# Li-Fi_Receiver_Schematic.net
KiCad netlist of a schematic drawn in EAGLE
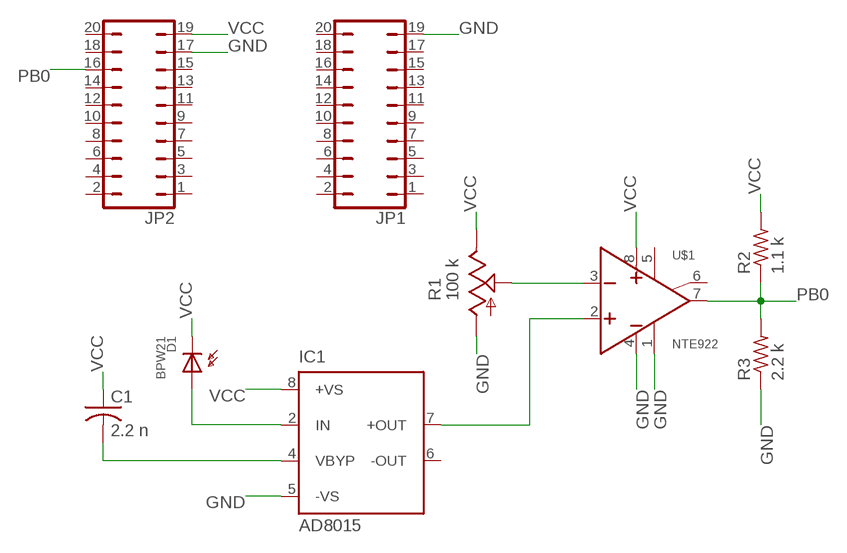
[diagram p0: schematic, sheet 1]

(export (version "E")
  (design (tool "Eeschema 10.0.6"))
  (components
    (comp (ref "C1")
      (value "2.2 n")
      (footprint "eagle-import:C0805")
      (libsource (lib "eagle-import") (part "C-USC0805"))
    )
    (comp (ref "D1")
      (value "BPW21")
      (footprint "eagle-import:TO-5")
      (libsource (lib "eagle-import") (part "BPW21"))
    )
    (comp (ref "IC1")
      (value "AD8015")
      (footprint "eagle-import:SO8")
      (fields (field (name "MPN") "AD8015ARZ"))
      (libsource (lib "eagle-import") (part "AD8015"))
    )
    (comp (ref "JP1")
      (value "JP10Q")
      (footprint "eagle-import:JP10Q")
      (libsource (lib "eagle-import") (part "JP10Q"))
    )
    (comp (ref "JP2")
      (value "JP10Q")
      (footprint "eagle-import:JP10Q")
      (libsource (lib "eagle-import") (part "JP10Q"))
    )
    (comp (ref "R1")
      (value "100 k")
      (footprint "eagle-import:B64Y")
      (libsource (lib "eagle-import") (part "TRIM_US-B64Y"))
    )
    (comp (ref "R2")
      (value "1.1 k")
      (footprint "eagle-import:M0805")
      (libsource (lib "eagle-import") (part "R-US_M0805"))
    )
    (comp (ref "R3")
      (value "2.2 k")
      (footprint "eagle-import:M0805")
      (libsource (lib "eagle-import") (part "R-US_M0805"))
    )
    (comp (ref "U$1")
      (value "NTE922")
      (footprint "eagle-import:DIP8")
      (libsource (lib "eagle-import") (part "NTE922"))
    )
  )
  (nets
    (net (code "1") (name "/GND") (class "Default")
      (node (ref "IC1") (pin "5") (pinfunction "-VS_5") (pintype "input"))
      (node (ref "JP1") (pin "19") (pinfunction "19_19") (pintype "passive"))
      (node (ref "JP2") (pin "17") (pinfunction "17_17") (pintype "passive"))
      (node (ref "R1") (pin "A") (pinfunction "A_A") (pintype "passive"))
      (node (ref "R3") (pin "1") (pinfunction "1_1") (pintype "passive"))
      (node (ref "U$1") (pin "1") (pinfunction "1_1") (pintype "bidirectional"))
      (node (ref "U$1") (pin "4") (pinfunction "4_4") (pintype "bidirectional"))
    )
    (net (code "2") (name "/PB0") (class "Default")
      (node (ref "JP2") (pin "16") (pinfunction "16_16") (pintype "passive"))
      (node (ref "R2") (pin "1") (pinfunction "1_1") (pintype "passive"))
      (node (ref "R3") (pin "2") (pinfunction "2_2") (pintype "passive"))
      (node (ref "U$1") (pin "7") (pinfunction "7_7") (pintype "bidirectional"))
    )
    (net (code "3") (name "/VCC") (class "Default")
      (node (ref "C1") (pin "1") (pinfunction "1_1") (pintype "passive"))
      (node (ref "D1") (pin "CATH") (pinfunction "CATH_CATH") (pintype "bidirectional"))
      (node (ref "IC1") (pin "8") (pinfunction "+VS_8") (pintype "input"))
      (node (ref "JP2") (pin "19") (pinfunction "19_19") (pintype "passive"))
      (node (ref "R1") (pin "E") (pinfunction "E_E") (pintype "passive"))
      (node (ref "R2") (pin "2") (pinfunction "2_2") (pintype "passive"))
      (node (ref "U$1") (pin "8") (pinfunction "8_8") (pintype "bidirectional"))
    )
    (net (code "4") (name "Net-(IC1-+OUT)") (class "Default")
      (node (ref "IC1") (pin "7") (pinfunction "+OUT_7") (pintype "output"))
      (node (ref "U$1") (pin "2") (pinfunction "2_2") (pintype "bidirectional"))
    )
    (net (code "5") (name "Net-(IC1-IN)") (class "Default")
      (node (ref "D1") (pin "AN") (pinfunction "AN_AN") (pintype "bidirectional"))
      (node (ref "IC1") (pin "2") (pinfunction "IN_2") (pintype "input"))
    )
    (net (code "6") (name "Net-(IC1-VBYP)") (class "Default")
      (node (ref "C1") (pin "2") (pinfunction "2_2") (pintype "passive"))
      (node (ref "IC1") (pin "4") (pinfunction "VBYP_4") (pintype "input"))
    )
    (net (code "7") (name "Net-(R1-PadS)") (class "Default")
      (node (ref "R1") (pin "S") (pinfunction "S_S") (pintype "passive"))
      (node (ref "U$1") (pin "3") (pinfunction "3_3") (pintype "bidirectional"))
    )
    (net (code "8") (name "unconnected-(IC1--OUT-Pad6)") (class "Default")
      (node (ref "IC1") (pin "6") (pinfunction "-OUT_6") (pintype "output"))
    )
    (net (code "9") (name "unconnected-(JP1-Pad1)") (class "Default")
      (node (ref "JP1") (pin "1") (pinfunction "1_1") (pintype "passive"))
    )
    (net (code "10") (name "unconnected-(JP1-Pad2)") (class "Default")
      (node (ref "JP1") (pin "2") (pinfunction "2_2") (pintype "passive"))
    )
    (net (code "11") (name "unconnected-(JP1-Pad3)") (class "Default")
      (node (ref "JP1") (pin "3") (pinfunction "3_3") (pintype "passive"))
    )
    (net (code "12") (name "unconnected-(JP1-Pad4)") (class "Default")
      (node (ref "JP1") (pin "4") (pinfunction "4_4") (pintype "passive"))
    )
    (net (code "13") (name "unconnected-(JP1-Pad5)") (class "Default")
      (node (ref "JP1") (pin "5") (pinfunction "5_5") (pintype "passive"))
    )
    (net (code "14") (name "unconnected-(JP1-Pad6)") (class "Default")
      (node (ref "JP1") (pin "6") (pinfunction "6_6") (pintype "passive"))
    )
    (net (code "15") (name "unconnected-(JP1-Pad7)") (class "Default")
      (node (ref "JP1") (pin "7") (pinfunction "7_7") (pintype "passive"))
    )
    (net (code "16") (name "unconnected-(JP1-Pad8)") (class "Default")
      (node (ref "JP1") (pin "8") (pinfunction "8_8") (pintype "passive"))
    )
    (net (code "17") (name "unconnected-(JP1-Pad9)") (class "Default")
      (node (ref "JP1") (pin "9") (pinfunction "9_9") (pintype "passive"))
    )
    (net (code "18") (name "unconnected-(JP1-Pad10)") (class "Default")
      (node (ref "JP1") (pin "10") (pinfunction "10_10") (pintype "passive"))
    )
    (net (code "19") (name "unconnected-(JP1-Pad11)") (class "Default")
      (node (ref "JP1") (pin "11") (pinfunction "11_11") (pintype "passive"))
    )
    (net (code "20") (name "unconnected-(JP1-Pad12)") (class "Default")
      (node (ref "JP1") (pin "12") (pinfunction "12_12") (pintype "passive"))
    )
    (net (code "21") (name "unconnected-(JP1-Pad13)") (class "Default")
      (node (ref "JP1") (pin "13") (pinfunction "13_13") (pintype "passive"))
    )
    (net (code "22") (name "unconnected-(JP1-Pad14)") (class "Default")
      (node (ref "JP1") (pin "14") (pinfunction "14_14") (pintype "passive"))
    )
    (net (code "23") (name "unconnected-(JP1-Pad15)") (class "Default")
      (node (ref "JP1") (pin "15") (pinfunction "15_15") (pintype "passive"))
    )
    (net (code "24") (name "unconnected-(JP1-Pad16)") (class "Default")
      (node (ref "JP1") (pin "16") (pinfunction "16_16") (pintype "passive"))
    )
    (net (code "25") (name "unconnected-(JP1-Pad17)") (class "Default")
      (node (ref "JP1") (pin "17") (pinfunction "17_17") (pintype "passive"))
    )
    (net (code "26") (name "unconnected-(JP1-Pad18)") (class "Default")
      (node (ref "JP1") (pin "18") (pinfunction "18_18") (pintype "passive"))
    )
    (net (code "27") (name "unconnected-(JP1-Pad20)") (class "Default")
      (node (ref "JP1") (pin "20") (pinfunction "20_20") (pintype "passive"))
    )
    (net (code "28") (name "unconnected-(JP2-Pad1)") (class "Default")
      (node (ref "JP2") (pin "1") (pinfunction "1_1") (pintype "passive"))
    )
    (net (code "29") (name "unconnected-(JP2-Pad2)") (class "Default")
      (node (ref "JP2") (pin "2") (pinfunction "2_2") (pintype "passive"))
    )
    (net (code "30") (name "unconnected-(JP2-Pad3)") (class "Default")
      (node (ref "JP2") (pin "3") (pinfunction "3_3") (pintype "passive"))
    )
    (net (code "31") (name "unconnected-(JP2-Pad4)") (class "Default")
      (node (ref "JP2") (pin "4") (pinfunction "4_4") (pintype "passive"))
    )
    (net (code "32") (name "unconnected-(JP2-Pad5)") (class "Default")
      (node (ref "JP2") (pin "5") (pinfunction "5_5") (pintype "passive"))
    )
    (net (code "33") (name "unconnected-(JP2-Pad6)") (class "Default")
      (node (ref "JP2") (pin "6") (pinfunction "6_6") (pintype "passive"))
    )
    (net (code "34") (name "unconnected-(JP2-Pad7)") (class "Default")
      (node (ref "JP2") (pin "7") (pinfunction "7_7") (pintype "passive"))
    )
    (net (code "35") (name "unconnected-(JP2-Pad8)") (class "Default")
      (node (ref "JP2") (pin "8") (pinfunction "8_8") (pintype "passive"))
    )
    (net (code "36") (name "unconnected-(JP2-Pad9)") (class "Default")
      (node (ref "JP2") (pin "9") (pinfunction "9_9") (pintype "passive"))
    )
    (net (code "37") (name "unconnected-(JP2-Pad10)") (class "Default")
      (node (ref "JP2") (pin "10") (pinfunction "10_10") (pintype "passive"))
    )
    (net (code "38") (name "unconnected-(JP2-Pad11)") (class "Default")
      (node (ref "JP2") (pin "11") (pinfunction "11_11") (pintype "passive"))
    )
    (net (code "39") (name "unconnected-(JP2-Pad12)") (class "Default")
      (node (ref "JP2") (pin "12") (pinfunction "12_12") (pintype "passive"))
    )
    (net (code "40") (name "unconnected-(JP2-Pad13)") (class "Default")
      (node (ref "JP2") (pin "13") (pinfunction "13_13") (pintype "passive"))
    )
    (net (code "41") (name "unconnected-(JP2-Pad14)") (class "Default")
      (node (ref "JP2") (pin "14") (pinfunction "14_14") (pintype "passive"))
    )
    (net (code "42") (name "unconnected-(JP2-Pad15)") (class "Default")
      (node (ref "JP2") (pin "15") (pinfunction "15_15") (pintype "passive"))
    )
    (net (code "43") (name "unconnected-(JP2-Pad18)") (class "Default")
      (node (ref "JP2") (pin "18") (pinfunction "18_18") (pintype "passive"))
    )
    (net (code "44") (name "unconnected-(JP2-Pad20)") (class "Default")
      (node (ref "JP2") (pin "20") (pinfunction "20_20") (pintype "passive"))
    )
    (net (code "45") (name "unconnected-(U$1-Pad5)") (class "Default")
      (node (ref "U$1") (pin "5") (pinfunction "5_5") (pintype "bidirectional"))
    )
    (net (code "46") (name "unconnected-(U$1-Pad6)") (class "Default")
      (node (ref "U$1") (pin "6") (pinfunction "6_6") (pintype "bidirectional"))
    )
  )
)
